# tiny13devboard.net
KiCad netlist of a schematic drawn in EAGLE
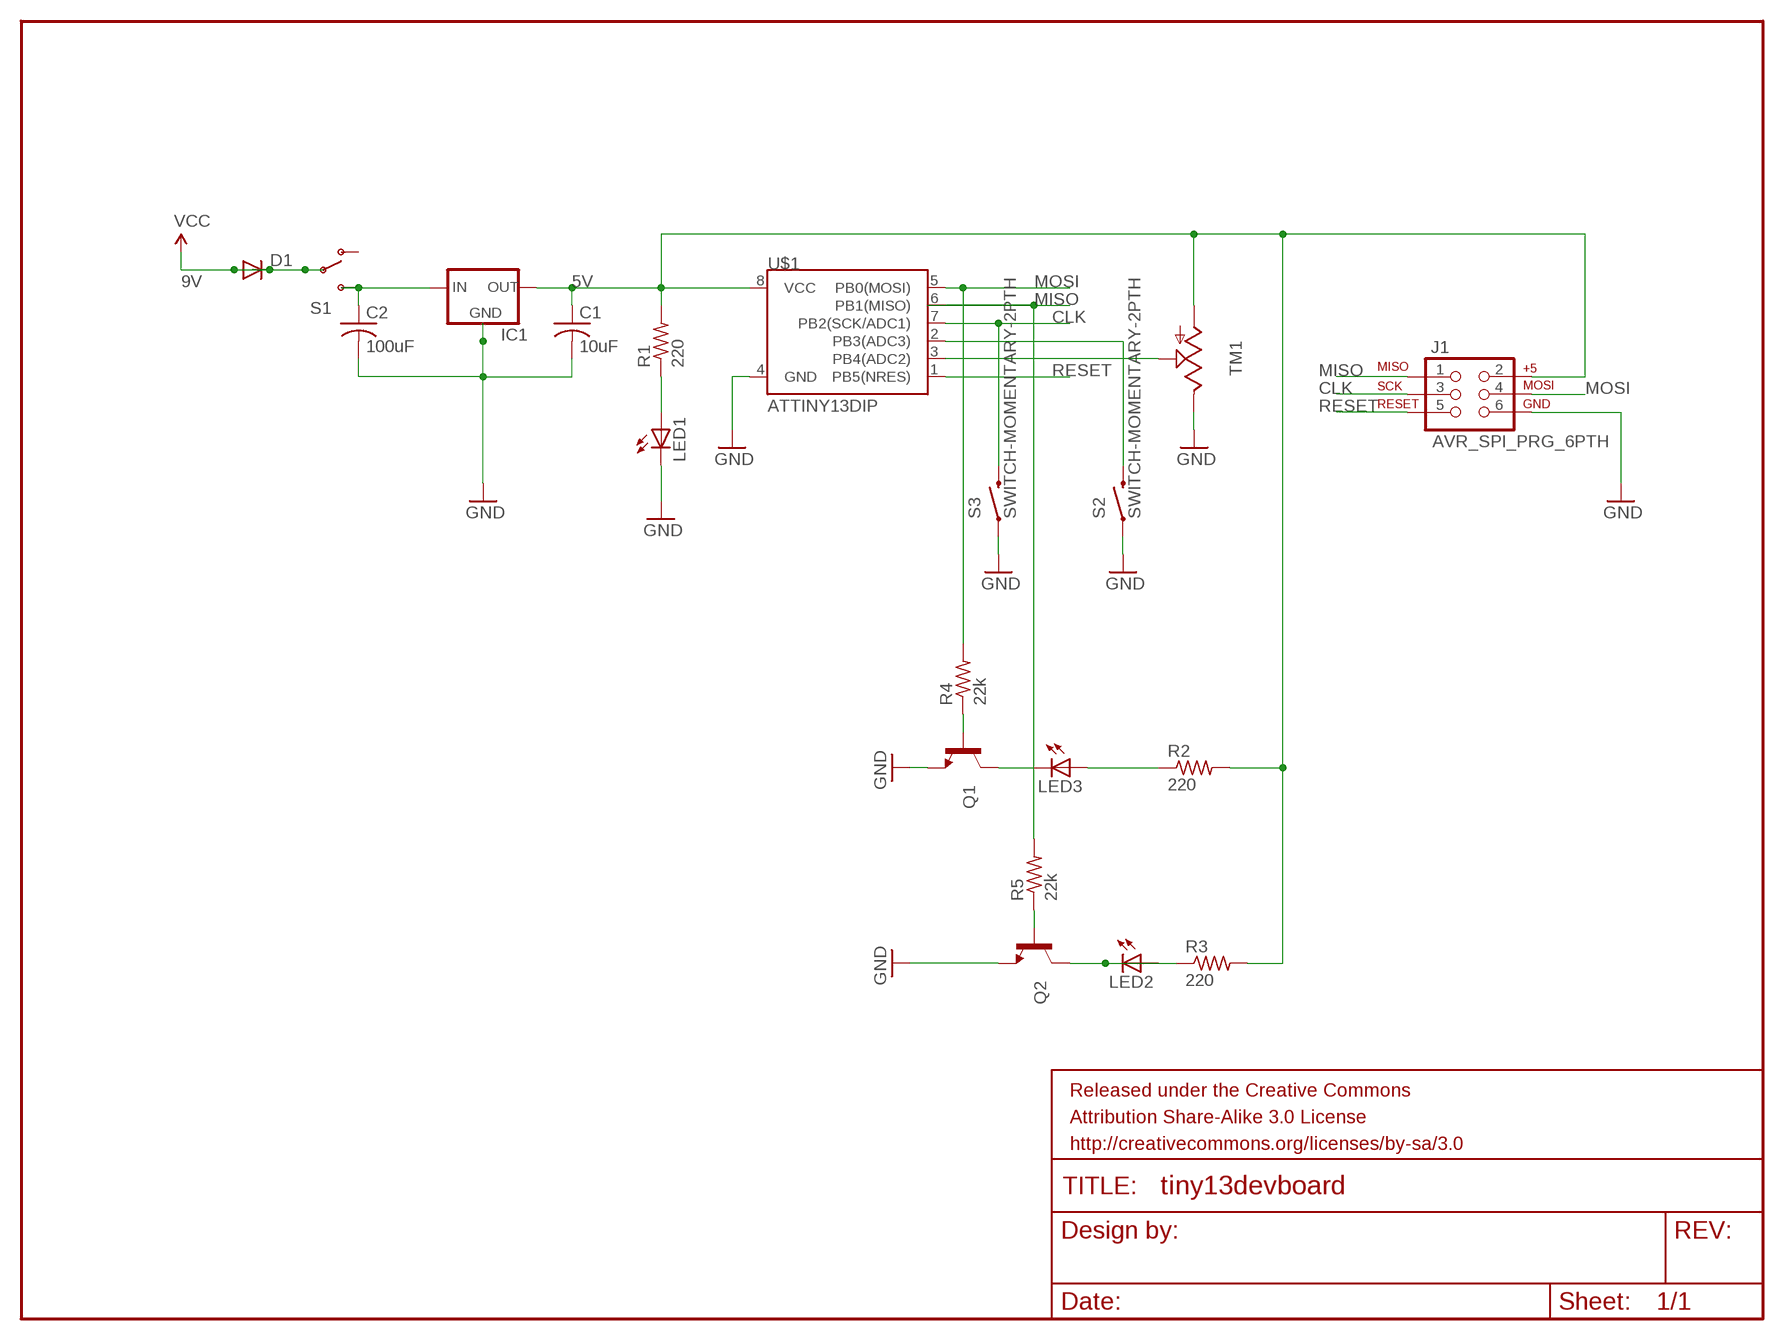
[diagram p0: schematic, sheet 1]

(export (version "E")
  (design (tool "Eeschema 10.0.6"))
  (components
    (comp (ref "C1")
      (value "10uF")
      (footprint "eagle-import:C050-025X075")
      (libsource (lib "eagle-import") (part "C-US050-025X075"))
    )
    (comp (ref "C2")
      (value "100uF")
      (footprint "eagle-import:C050-025X075")
      (libsource (lib "eagle-import") (part "C-US050-025X075"))
    )
    (comp (ref "D1")
      (value "DIODEPTH")
      (footprint "eagle-import:DIODE-1N4001")
      (libsource (lib "eagle-import") (part "DIODEPTH"))
    )
    (comp (ref "FRAME1")
      (value "FRAME-LETTER")
      (footprint "eagle-import:CREATIVE_COMMONS")
      (libsource (lib "eagle-import") (part "FRAME-LETTER"))
    )
    (comp (ref "IC1")
      (value "V_REG_78XX-TO-220")
      (footprint "eagle-import:TO-220-ALT")
      (libsource (lib "eagle-import") (part "V_REG_78XX-TO-220"))
    )
    (comp (ref "J1")
      (value "AVR_SPI_PRG_6PTH")
      (footprint "eagle-import:2X3")
      (libsource (lib "eagle-import") (part "AVR_SPI_PRG_6PTH"))
    )
    (comp (ref "LED1")
      (value "LED5MM")
      (footprint "eagle-import:LED5MM")
      (libsource (lib "eagle-import") (part "LED5MM"))
    )
    (comp (ref "LED2")
      (value "LED5MM")
      (footprint "eagle-import:LED5MM")
      (libsource (lib "eagle-import") (part "LED5MM"))
    )
    (comp (ref "LED3")
      (value "LED5MM")
      (footprint "eagle-import:LED5MM")
      (libsource (lib "eagle-import") (part "LED5MM"))
    )
    (comp (ref "Q1")
      (value "TRANSISTOR_NPNTO92")
      (footprint "eagle-import:TO-92")
      (libsource (lib "eagle-import") (part "TRANSISTOR_NPNTO92"))
    )
    (comp (ref "Q2")
      (value "TRANSISTOR_NPNTO92")
      (footprint "eagle-import:TO-92")
      (libsource (lib "eagle-import") (part "TRANSISTOR_NPNTO92"))
    )
    (comp (ref "R1")
      (value "220")
      (footprint "eagle-import:0207_10")
      (libsource (lib "eagle-import") (part "R-US_0207/10"))
    )
    (comp (ref "R2")
      (value "220")
      (footprint "eagle-import:0207_10")
      (libsource (lib "eagle-import") (part "R-US_0207/10"))
    )
    (comp (ref "R3")
      (value "220")
      (footprint "eagle-import:0207_10")
      (libsource (lib "eagle-import") (part "R-US_0207/10"))
    )
    (comp (ref "R4")
      (value "22k")
      (footprint "eagle-import:0207_10")
      (libsource (lib "eagle-import") (part "R-US_0207/10"))
    )
    (comp (ref "R5")
      (value "22k")
      (footprint "eagle-import:0207_10")
      (libsource (lib "eagle-import") (part "R-US_0207/10"))
    )
    (comp (ref "S1")
      (value "SWITCH-SPDTPTH")
      (footprint "eagle-import:SWITCH-SPDT")
      (libsource (lib "eagle-import") (part "SWITCH-SPDTPTH"))
    )
    (comp (ref "S2")
      (value "SWITCH-MOMENTARY-2PTH")
      (footprint "eagle-import:TACTILE-PTH")
      (libsource (lib "eagle-import") (part "SWITCH-MOMENTARY-2PTH"))
    )
    (comp (ref "S3")
      (value "SWITCH-MOMENTARY-2PTH")
      (footprint "eagle-import:TACTILE-PTH")
      (libsource (lib "eagle-import") (part "SWITCH-MOMENTARY-2PTH"))
    )
    (comp (ref "TM1")
      (value "TRIM")
      (footprint "eagle-import:6MM")
      (libsource (lib "eagle-import") (part "TRIM"))
    )
    (comp (ref "U$1")
      (value "ATTINY13DIP")
      (footprint "eagle-import:DIP08")
      (libsource (lib "eagle-import") (part "ATTINY13DIP"))
    )
  )
  (nets
    (net (code "1") (name "/5V") (class "Default")
      (node (ref "C1") (pin "1") (pinfunction "1_1") (pintype "passive"))
      (node (ref "IC1") (pin "OUT") (pinfunction "OUT_OUT") (pintype "output"))
      (node (ref "J1") (pin "2") (pinfunction "2_2") (pintype "passive"))
      (node (ref "R1") (pin "2") (pinfunction "2_2") (pintype "passive"))
      (node (ref "R2") (pin "2") (pinfunction "2_2") (pintype "passive"))
      (node (ref "R3") (pin "2") (pinfunction "2_2") (pintype "passive"))
      (node (ref "TM1") (pin "A") (pinfunction "A_A") (pintype "passive"))
      (node (ref "U$1") (pin "8") (pinfunction "VCC_8") (pintype "bidirectional"))
    )
    (net (code "2") (name "/CLK") (class "Default")
      (node (ref "J1") (pin "3") (pinfunction "3_3") (pintype "passive"))
      (node (ref "S3") (pin "3") (pinfunction "2_3") (pintype "passive"))
      (node (ref "U$1") (pin "7") (pinfunction "PB2(SCK/ADC1)_7") (pintype "bidirectional"))
    )
    (net (code "3") (name "/MISO") (class "Default")
      (node (ref "J1") (pin "1") (pinfunction "1_1") (pintype "passive"))
      (node (ref "R5") (pin "2") (pinfunction "2_2") (pintype "passive"))
      (node (ref "U$1") (pin "6") (pinfunction "PB1(MISO)_6") (pintype "bidirectional"))
    )
    (net (code "4") (name "/MOSI") (class "Default")
      (node (ref "J1") (pin "4") (pinfunction "4_4") (pintype "passive"))
      (node (ref "R4") (pin "2") (pinfunction "2_2") (pintype "passive"))
      (node (ref "U$1") (pin "5") (pinfunction "PB0(MOSI)_5") (pintype "bidirectional"))
    )
    (net (code "5") (name "/RESET") (class "Default")
      (node (ref "J1") (pin "5") (pinfunction "5_5") (pintype "passive"))
      (node (ref "U$1") (pin "1") (pinfunction "PB5(NRES)_1") (pintype "bidirectional"))
    )
    (net (code "6") (name "GND") (class "Default")
      (node (ref "C1") (pin "2") (pinfunction "2_2") (pintype "passive"))
      (node (ref "C2") (pin "2") (pinfunction "2_2") (pintype "passive"))
      (node (ref "IC1") (pin "GND") (pinfunction "GND_GND") (pintype "input"))
      (node (ref "J1") (pin "6") (pinfunction "6_6") (pintype "passive"))
      (node (ref "LED1") (pin "K") (pinfunction "C_K") (pintype "passive"))
      (node (ref "Q1") (pin "1") (pinfunction "E_1") (pintype "passive"))
      (node (ref "Q2") (pin "1") (pinfunction "E_1") (pintype "passive"))
      (node (ref "S2") (pin "1") (pinfunction "1_1") (pintype "passive"))
      (node (ref "S3") (pin "1") (pinfunction "1_1") (pintype "passive"))
      (node (ref "TM1") (pin "E") (pinfunction "E_E") (pintype "passive"))
      (node (ref "U$1") (pin "4") (pinfunction "GND_4") (pintype "bidirectional"))
    )
    (net (code "7") (name "Net-(LED1-PadA)") (class "Default")
      (node (ref "LED1") (pin "A") (pinfunction "A_A") (pintype "passive"))
      (node (ref "R1") (pin "1") (pinfunction "1_1") (pintype "passive"))
    )
    (net (code "8") (name "Net-(LED2-C)") (class "Default")
      (node (ref "LED2") (pin "A") (pinfunction "A_A") (pintype "passive"))
      (node (ref "LED2") (pin "K") (pinfunction "C_K") (pintype "passive"))
      (node (ref "Q2") (pin "3") (pinfunction "C_3") (pintype "passive"))
      (node (ref "R3") (pin "1") (pinfunction "1_1") (pintype "passive"))
    )
    (net (code "9") (name "Net-(LED3-C)") (class "Default")
      (node (ref "LED3") (pin "K") (pinfunction "C_K") (pintype "passive"))
      (node (ref "Q1") (pin "3") (pinfunction "C_3") (pintype "passive"))
    )
    (net (code "10") (name "Net-(LED3-PadA)") (class "Default")
      (node (ref "LED3") (pin "A") (pinfunction "A_A") (pintype "passive"))
      (node (ref "R2") (pin "1") (pinfunction "1_1") (pintype "passive"))
    )
    (net (code "11") (name "Net-(Q1-B)") (class "Default")
      (node (ref "Q1") (pin "2") (pinfunction "B_2") (pintype "passive"))
      (node (ref "R4") (pin "1") (pinfunction "1_1") (pintype "passive"))
    )
    (net (code "12") (name "Net-(Q2-B)") (class "Default")
      (node (ref "Q2") (pin "2") (pinfunction "B_2") (pintype "passive"))
      (node (ref "R5") (pin "1") (pinfunction "1_1") (pintype "passive"))
    )
    (net (code "13") (name "Net-(S1-S)") (class "Default")
      (node (ref "C2") (pin "1") (pinfunction "1_1") (pintype "passive"))
      (node (ref "IC1") (pin "IN") (pinfunction "IN_IN") (pintype "input"))
      (node (ref "S1") (pin "3") (pinfunction "S_3") (pintype "passive"))
    )
    (net (code "14") (name "Net-(S2-2)") (class "Default")
      (node (ref "S2") (pin "3") (pinfunction "2_3") (pintype "passive"))
      (node (ref "U$1") (pin "2") (pinfunction "PB3(ADC3)_2") (pintype "bidirectional"))
    )
    (net (code "15") (name "Net-(U$1-PB4(ADC2))") (class "Default")
      (node (ref "TM1") (pin "S") (pinfunction "S_S") (pintype "passive"))
      (node (ref "U$1") (pin "3") (pinfunction "PB4(ADC2)_3") (pintype "bidirectional"))
    )
    (net (code "16") (name "VCC") (class "Default")
      (node (ref "D1") (pin "A") (pinfunction "A_A") (pintype "passive"))
      (node (ref "D1") (pin "C") (pinfunction "C_C") (pintype "passive"))
      (node (ref "S1") (pin "2") (pinfunction "P_2") (pintype "passive"))
    )
    (net (code "17") (name "unconnected-(S1-O-Pad1)") (class "Default")
      (node (ref "S1") (pin "1") (pinfunction "O_1") (pintype "passive"))
    )
  )
)
